# main_8.net
KiCad netlist of a schematic drawn in Altium Designer
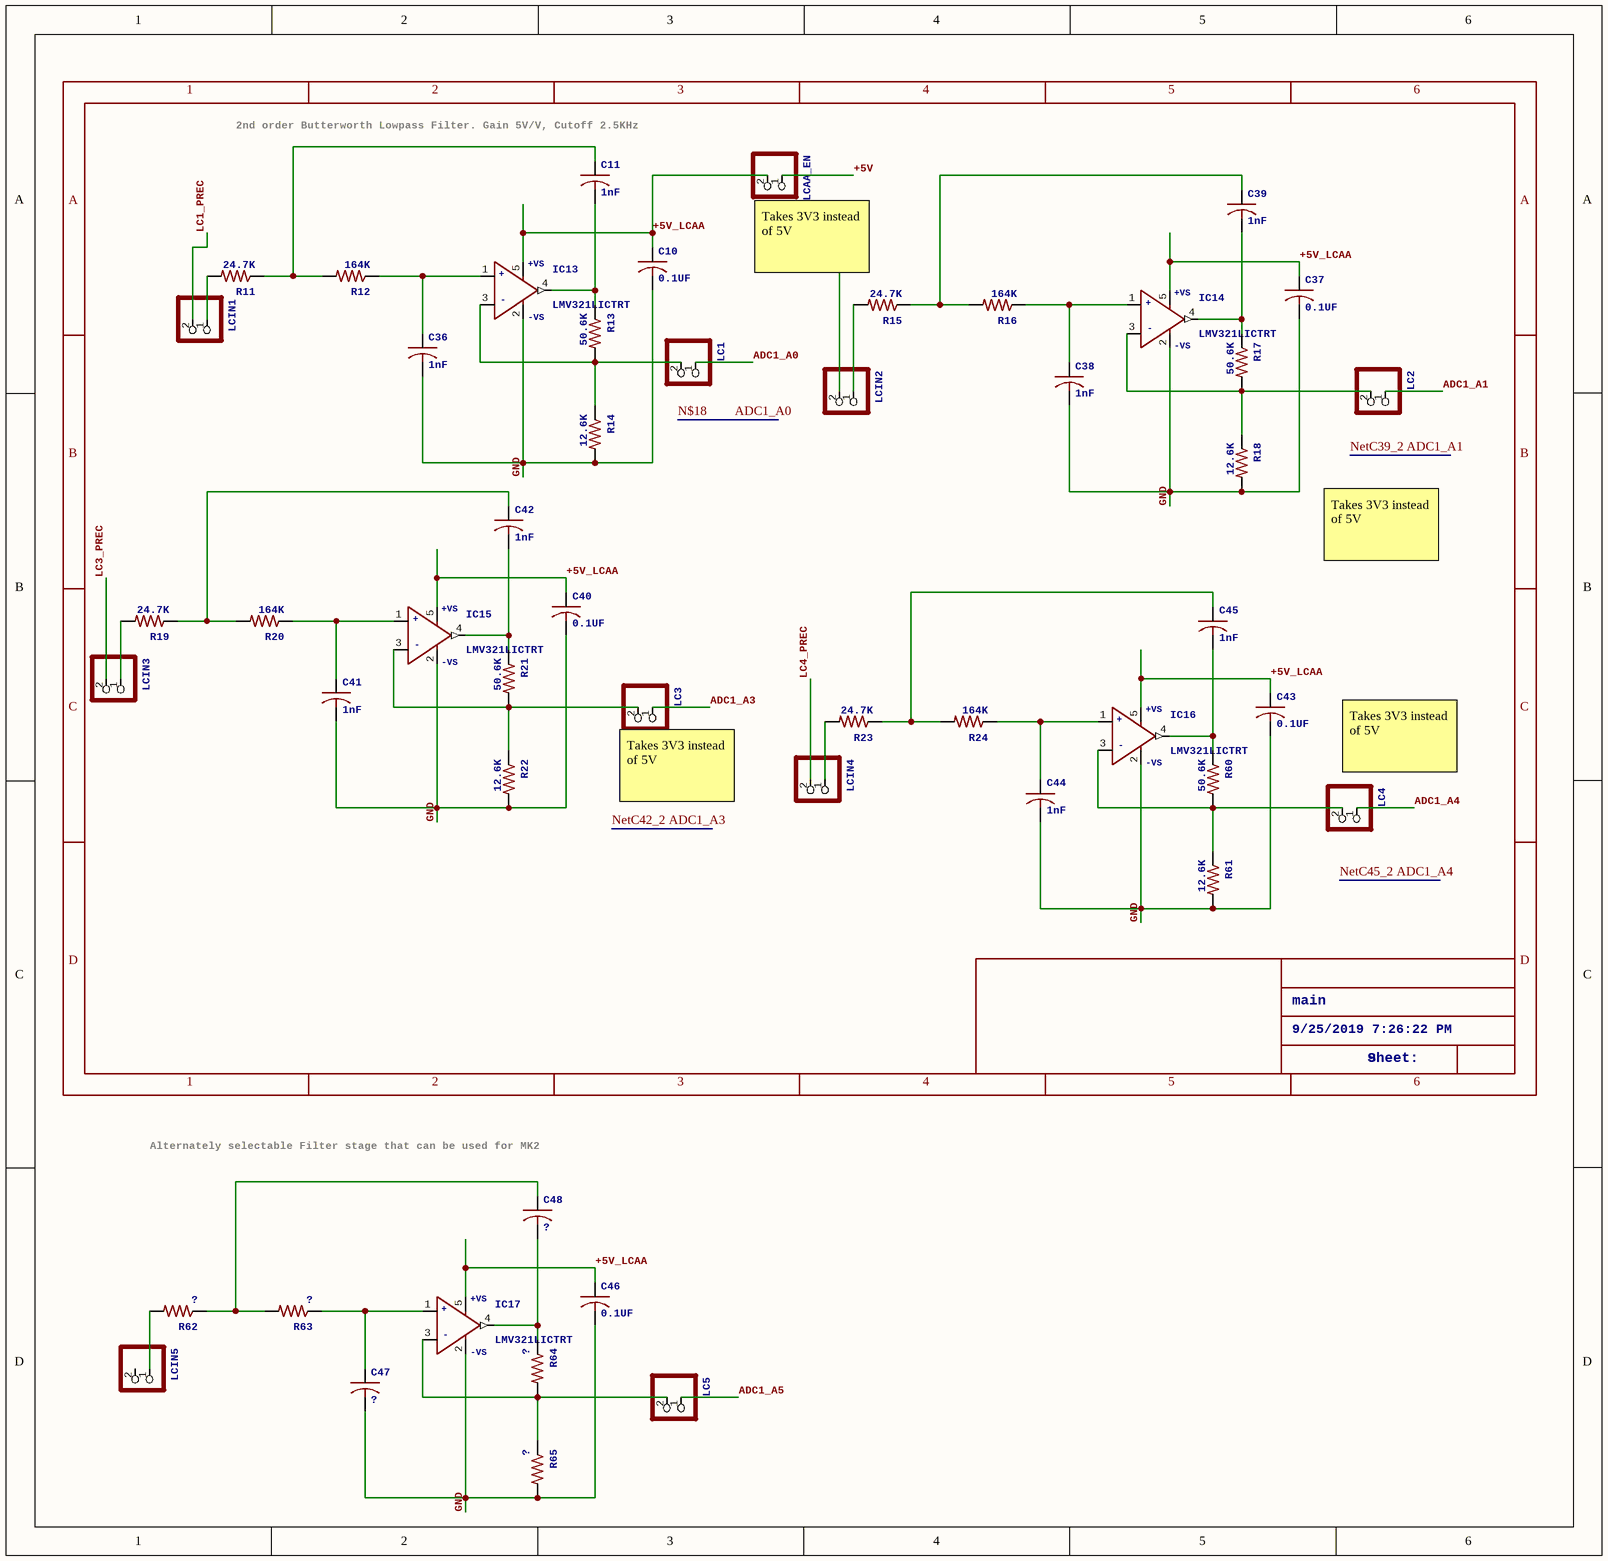
[diagram p0: main_8.SchDoc]

(export (version "E")
  (design (tool "Eeschema 10.0.6"))
  (components
    (comp (ref "C10")
      (value "0.1UF")
      (footprint "C0805")
      (description "CAPACITOR, American symbol")
      (libsource (lib "rcl") (part "C-USC0805"))
    )
    (comp (ref "C11")
      (value "1nF")
      (footprint "C0805")
      (description "CAPACITOR, American symbol")
      (libsource (lib "rcl") (part "C-USC0805"))
    )
    (comp (ref "C36")
      (value "1nF")
      (footprint "C0805")
      (description "CAPACITOR, American symbol")
      (libsource (lib "rcl") (part "C-USC0805"))
    )
    (comp (ref "C37")
      (value "0.1UF")
      (footprint "C0805")
      (description "CAPACITOR, American symbol")
      (libsource (lib "rcl") (part "C-USC0805"))
    )
    (comp (ref "C38")
      (value "1nF")
      (footprint "C0805")
      (description "CAPACITOR, American symbol")
      (libsource (lib "rcl") (part "C-USC0805"))
    )
    (comp (ref "C39")
      (value "1nF")
      (footprint "C0805")
      (description "CAPACITOR, American symbol")
      (libsource (lib "rcl") (part "C-USC0805"))
    )
    (comp (ref "C40")
      (value "0.1UF")
      (footprint "C0805")
      (description "CAPACITOR, American symbol")
      (libsource (lib "rcl") (part "C-USC0805"))
    )
    (comp (ref "C41")
      (value "1nF")
      (footprint "C0805")
      (description "CAPACITOR, American symbol")
      (libsource (lib "rcl") (part "C-USC0805"))
    )
    (comp (ref "C42")
      (value "1nF")
      (footprint "C0805")
      (description "CAPACITOR, American symbol")
      (libsource (lib "rcl") (part "C-USC0805"))
    )
    (comp (ref "C43")
      (value "0.1UF")
      (footprint "C0805")
      (description "CAPACITOR, American symbol")
      (libsource (lib "rcl") (part "C-USC0805"))
    )
    (comp (ref "C44")
      (value "1nF")
      (footprint "C0805")
      (description "CAPACITOR, American symbol")
      (libsource (lib "rcl") (part "C-USC0805"))
    )
    (comp (ref "C45")
      (value "1nF")
      (footprint "C0805")
      (description "CAPACITOR, American symbol")
      (libsource (lib "rcl") (part "C-USC0805"))
    )
    (comp (ref "C46")
      (value "0.1UF")
      (footprint "C0805")
      (description "CAPACITOR, American symbol")
      (libsource (lib "rcl") (part "C-USC0805"))
    )
    (comp (ref "C47")
      (value "?")
      (footprint "C0805")
      (description "CAPACITOR, American symbol")
      (libsource (lib "rcl") (part "C-USC0805"))
    )
    (comp (ref "C48")
      (value "?")
      (footprint "C0805")
      (description "CAPACITOR, American symbol")
      (libsource (lib "rcl") (part "C-USC0805"))
    )
    (comp (ref "IC13")
      (value "LMV321LICTRT")
      (footprint "SOT23-5")
      (fields
        (field (name "MF") "ALTERA CORPORATION")
        (field (name "MPN") "AD8065ARTZ-REEL7")
        (field (name "+") "+")
        (field (name "-") "-")
        (field (name "+VS") "+VS")
        (field (name "-VS") "-VS")
        (field (name "LIBRARYNAME") "st-microelectronics-extra")
      )
      (libsource (lib "st-microelectronics-extra") (part "LMV321LICTRT"))
    )
    (comp (ref "IC14")
      (value "LMV321LICTRT")
      (footprint "SOT23-5")
      (fields
        (field (name "MF") "ALTERA CORPORATION")
        (field (name "MPN") "AD8065ARTZ-REEL7")
        (field (name "+") "+")
        (field (name "-") "-")
        (field (name "+VS") "+VS")
        (field (name "-VS") "-VS")
        (field (name "LIBRARYNAME") "st-microelectronics-extra")
      )
      (libsource (lib "st-microelectronics-extra") (part "LMV321LICTRT"))
    )
    (comp (ref "IC15")
      (value "LMV321LICTRT")
      (footprint "SOT23-5")
      (fields
        (field (name "MF") "ALTERA CORPORATION")
        (field (name "MPN") "AD8065ARTZ-REEL7")
        (field (name "+") "+")
        (field (name "-") "-")
        (field (name "+VS") "+VS")
        (field (name "-VS") "-VS")
        (field (name "LIBRARYNAME") "st-microelectronics-extra")
      )
      (libsource (lib "st-microelectronics-extra") (part "LMV321LICTRT"))
    )
    (comp (ref "IC16")
      (value "LMV321LICTRT")
      (footprint "SOT23-5")
      (fields
        (field (name "MF") "ALTERA CORPORATION")
        (field (name "MPN") "AD8065ARTZ-REEL7")
        (field (name "+") "+")
        (field (name "-") "-")
        (field (name "+VS") "+VS")
        (field (name "-VS") "-VS")
        (field (name "LIBRARYNAME") "st-microelectronics-extra")
      )
      (libsource (lib "st-microelectronics-extra") (part "LMV321LICTRT"))
    )
    (comp (ref "IC17")
      (value "LMV321LICTRT")
      (footprint "SOT23-5")
      (fields
        (field (name "MF") "ALTERA CORPORATION")
        (field (name "MPN") "AD8065ARTZ-REEL7")
        (field (name "+") "+")
        (field (name "-") "-")
        (field (name "+VS") "+VS")
        (field (name "-VS") "-VS")
        (field (name "LIBRARYNAME") "st-microelectronics-extra")
      )
      (libsource (lib "st-microelectronics-extra") (part "LMV321LICTRT"))
    )
    (comp (ref "LC1")
      (value "PINHD-1X2")
      (footprint "1X02")
      (description "PIN HEADER")
      (fields (field (name "LIBRARYNAME") "pinhead"))
      (libsource (lib "pinhead") (part "PINHD-1X2"))
    )
    (comp (ref "LC2")
      (value "PINHD-1X2")
      (footprint "1X02")
      (description "PIN HEADER")
      (fields (field (name "LIBRARYNAME") "pinhead"))
      (libsource (lib "pinhead") (part "PINHD-1X2"))
    )
    (comp (ref "LC3")
      (value "PINHD-1X2")
      (footprint "1X02")
      (description "PIN HEADER")
      (fields (field (name "LIBRARYNAME") "pinhead"))
      (libsource (lib "pinhead") (part "PINHD-1X2"))
    )
    (comp (ref "LC4")
      (value "PINHD-1X2")
      (footprint "1X02")
      (description "PIN HEADER")
      (fields (field (name "LIBRARYNAME") "pinhead"))
      (libsource (lib "pinhead") (part "PINHD-1X2"))
    )
    (comp (ref "LC5")
      (value "PINHD-1X2")
      (footprint "1X02")
      (description "PIN HEADER")
      (fields (field (name "LIBRARYNAME") "pinhead"))
      (libsource (lib "pinhead") (part "PINHD-1X2"))
    )
    (comp (ref "LCAA_EN")
      (value "PINHD-1X2")
      (footprint "1X02")
      (description "PIN HEADER")
      (fields (field (name "LIBRARYNAME") "pinhead"))
      (libsource (lib "pinhead") (part "PINHD-1X2"))
    )
    (comp (ref "LCIN1")
      (value "PINHD-1X2")
      (footprint "1X02")
      (description "PIN HEADER")
      (fields (field (name "LIBRARYNAME") "pinhead"))
      (libsource (lib "pinhead") (part "PINHD-1X2"))
    )
    (comp (ref "LCIN2")
      (value "PINHD-1X2")
      (footprint "1X02")
      (description "PIN HEADER")
      (fields (field (name "LIBRARYNAME") "pinhead"))
      (libsource (lib "pinhead") (part "PINHD-1X2"))
    )
    (comp (ref "LCIN3")
      (value "PINHD-1X2")
      (footprint "1X02")
      (description "PIN HEADER")
      (fields (field (name "LIBRARYNAME") "pinhead"))
      (libsource (lib "pinhead") (part "PINHD-1X2"))
    )
    (comp (ref "LCIN4")
      (value "PINHD-1X2")
      (footprint "1X02")
      (description "PIN HEADER")
      (fields (field (name "LIBRARYNAME") "pinhead"))
      (libsource (lib "pinhead") (part "PINHD-1X2"))
    )
    (comp (ref "LCIN5")
      (value "PINHD-1X2")
      (footprint "1X02")
      (description "PIN HEADER")
      (fields (field (name "LIBRARYNAME") "pinhead"))
      (libsource (lib "pinhead") (part "PINHD-1X2"))
    )
    (comp (ref "R11")
      (value "24.7K")
      (footprint "R0805")
      (description "RESISTOR, American symbol")
      (libsource (lib "rcl") (part "R-US_R0805"))
    )
    (comp (ref "R12")
      (value "164K")
      (footprint "R0805")
      (description "RESISTOR, American symbol")
      (libsource (lib "rcl") (part "R-US_R0805"))
    )
    (comp (ref "R13")
      (value "50.6K")
      (footprint "R0805")
      (description "RESISTOR, American symbol")
      (libsource (lib "rcl") (part "R-US_R0805"))
    )
    (comp (ref "R14")
      (value "12.6K")
      (footprint "R0805")
      (description "RESISTOR, American symbol")
      (libsource (lib "rcl") (part "R-US_R0805"))
    )
    (comp (ref "R15")
      (value "24.7K")
      (footprint "R0805")
      (description "RESISTOR, American symbol")
      (libsource (lib "rcl") (part "R-US_R0805"))
    )
    (comp (ref "R16")
      (value "164K")
      (footprint "R0805")
      (description "RESISTOR, American symbol")
      (libsource (lib "rcl") (part "R-US_R0805"))
    )
    (comp (ref "R17")
      (value "50.6K")
      (footprint "R0805")
      (description "RESISTOR, American symbol")
      (libsource (lib "rcl") (part "R-US_R0805"))
    )
    (comp (ref "R18")
      (value "12.6K")
      (footprint "R0805")
      (description "RESISTOR, American symbol")
      (libsource (lib "rcl") (part "R-US_R0805"))
    )
    (comp (ref "R19")
      (value "24.7K")
      (footprint "R0805")
      (description "RESISTOR, American symbol")
      (libsource (lib "rcl") (part "R-US_R0805"))
    )
    (comp (ref "R20")
      (value "164K")
      (footprint "R0805")
      (description "RESISTOR, American symbol")
      (libsource (lib "rcl") (part "R-US_R0805"))
    )
    (comp (ref "R21")
      (value "50.6K")
      (footprint "R0805")
      (description "RESISTOR, American symbol")
      (libsource (lib "rcl") (part "R-US_R0805"))
    )
    (comp (ref "R22")
      (value "12.6K")
      (footprint "R0805")
      (description "RESISTOR, American symbol")
      (libsource (lib "rcl") (part "R-US_R0805"))
    )
    (comp (ref "R23")
      (value "24.7K")
      (footprint "R0805")
      (description "RESISTOR, American symbol")
      (libsource (lib "rcl") (part "R-US_R0805"))
    )
    (comp (ref "R24")
      (value "164K")
      (footprint "R0805")
      (description "RESISTOR, American symbol")
      (libsource (lib "rcl") (part "R-US_R0805"))
    )
    (comp (ref "R60")
      (value "50.6K")
      (footprint "R0805")
      (description "RESISTOR, American symbol")
      (libsource (lib "rcl") (part "R-US_R0805"))
    )
    (comp (ref "R61")
      (value "12.6K")
      (footprint "R0805")
      (description "RESISTOR, American symbol")
      (libsource (lib "rcl") (part "R-US_R0805"))
    )
    (comp (ref "R62")
      (value "?")
      (footprint "R0805")
      (description "RESISTOR, American symbol")
      (libsource (lib "rcl") (part "R-US_R0805"))
    )
    (comp (ref "R63")
      (value "?")
      (footprint "R0805")
      (description "RESISTOR, American symbol")
      (libsource (lib "rcl") (part "R-US_R0805"))
    )
    (comp (ref "R64")
      (value "?")
      (footprint "R0805")
      (description "RESISTOR, American symbol")
      (libsource (lib "rcl") (part "R-US_R0805"))
    )
    (comp (ref "R65")
      (value "?")
      (footprint "R0805")
      (description "RESISTOR, American symbol")
      (libsource (lib "rcl") (part "R-US_R0805"))
    )
  )
  (nets
    (net (code "1") (name "/+5V") (class "Default")
      (node (ref "LCAA_EN") (pin "1") (pinfunction "1_1") (pintype "passive"))
    )
    (net (code "2") (name "/+5V_LCAA") (class "Default")
      (node (ref "C10") (pin "1") (pinfunction "1_1") (pintype "passive"))
      (node (ref "C37") (pin "1") (pinfunction "1_1") (pintype "passive"))
      (node (ref "C40") (pin "1") (pinfunction "1_1") (pintype "passive"))
      (node (ref "C43") (pin "1") (pinfunction "1_1") (pintype "passive"))
      (node (ref "C46") (pin "1") (pinfunction "1_1") (pintype "passive"))
      (node (ref "IC13") (pin "5") (pinfunction "+VS_5") (pintype "passive"))
      (node (ref "IC14") (pin "5") (pinfunction "+VS_5") (pintype "passive"))
      (node (ref "IC15") (pin "5") (pinfunction "+VS_5") (pintype "passive"))
      (node (ref "IC16") (pin "5") (pinfunction "+VS_5") (pintype "passive"))
      (node (ref "IC17") (pin "5") (pinfunction "+VS_5") (pintype "passive"))
      (node (ref "LCAA_EN") (pin "2") (pinfunction "2_2") (pintype "passive"))
    )
    (net (code "3") (name "/ADC1_A0") (class "Default")
      (node (ref "LC1") (pin "1") (pinfunction "1_1") (pintype "passive"))
    )
    (net (code "4") (name "/ADC1_A1") (class "Default")
      (node (ref "LC2") (pin "1") (pinfunction "1_1") (pintype "passive"))
    )
    (net (code "5") (name "/ADC1_A3") (class "Default")
      (node (ref "LC3") (pin "1") (pinfunction "1_1") (pintype "passive"))
    )
    (net (code "6") (name "/ADC1_A4") (class "Default")
      (node (ref "LC4") (pin "1") (pinfunction "1_1") (pintype "passive"))
    )
    (net (code "7") (name "/ADC1_A5") (class "Default")
      (node (ref "LC5") (pin "1") (pinfunction "1_1") (pintype "passive"))
    )
    (net (code "8") (name "/GND") (class "Default")
      (node (ref "C10") (pin "2") (pinfunction "2_2") (pintype "passive"))
      (node (ref "C36") (pin "2") (pinfunction "2_2") (pintype "passive"))
      (node (ref "C37") (pin "2") (pinfunction "2_2") (pintype "passive"))
      (node (ref "C38") (pin "2") (pinfunction "2_2") (pintype "passive"))
      (node (ref "C40") (pin "2") (pinfunction "2_2") (pintype "passive"))
      (node (ref "C41") (pin "2") (pinfunction "2_2") (pintype "passive"))
      (node (ref "C43") (pin "2") (pinfunction "2_2") (pintype "passive"))
      (node (ref "C44") (pin "2") (pinfunction "2_2") (pintype "passive"))
      (node (ref "C46") (pin "2") (pinfunction "2_2") (pintype "passive"))
      (node (ref "C47") (pin "2") (pinfunction "2_2") (pintype "passive"))
      (node (ref "IC13") (pin "2") (pinfunction "-VS_2") (pintype "passive"))
      (node (ref "IC14") (pin "2") (pinfunction "-VS_2") (pintype "passive"))
      (node (ref "IC15") (pin "2") (pinfunction "-VS_2") (pintype "passive"))
      (node (ref "IC16") (pin "2") (pinfunction "-VS_2") (pintype "passive"))
      (node (ref "IC17") (pin "2") (pinfunction "-VS_2") (pintype "passive"))
      (node (ref "R14") (pin "2") (pinfunction "2_2") (pintype "passive"))
      (node (ref "R18") (pin "2") (pinfunction "2_2") (pintype "passive"))
      (node (ref "R22") (pin "2") (pinfunction "2_2") (pintype "passive"))
      (node (ref "R61") (pin "2") (pinfunction "2_2") (pintype "passive"))
      (node (ref "R65") (pin "2") (pinfunction "2_2") (pintype "passive"))
    )
    (net (code "9") (name "/LC1_PREC") (class "Default")
      (node (ref "LCIN1") (pin "2") (pinfunction "2_2") (pintype "passive"))
    )
    (net (code "10") (name "/LC2_PREC") (class "Default")
      (node (ref "LCIN2") (pin "2") (pinfunction "2_2") (pintype "passive"))
    )
    (net (code "11") (name "/LC3_PREC") (class "Default")
      (node (ref "LCIN3") (pin "2") (pinfunction "2_2") (pintype "passive"))
    )
    (net (code "12") (name "/LC4_PREC") (class "Default")
      (node (ref "LCIN4") (pin "2") (pinfunction "2_2") (pintype "passive"))
    )
    (net (code "13") (name "Net-(C11-Pad1)") (class "Default")
      (node (ref "C11") (pin "1") (pinfunction "1_1") (pintype "passive"))
      (node (ref "R11") (pin "1") (pinfunction "1_1") (pintype "passive"))
      (node (ref "R12") (pin "2") (pinfunction "2_2") (pintype "passive"))
    )
    (net (code "14") (name "Net-(C39-Pad1)") (class "Default")
      (node (ref "C39") (pin "1") (pinfunction "1_1") (pintype "passive"))
      (node (ref "R15") (pin "1") (pinfunction "1_1") (pintype "passive"))
      (node (ref "R16") (pin "2") (pinfunction "2_2") (pintype "passive"))
    )
    (net (code "15") (name "Net-(C42-Pad1)") (class "Default")
      (node (ref "C42") (pin "1") (pinfunction "1_1") (pintype "passive"))
      (node (ref "R19") (pin "1") (pinfunction "1_1") (pintype "passive"))
      (node (ref "R20") (pin "2") (pinfunction "2_2") (pintype "passive"))
    )
    (net (code "16") (name "Net-(C45-Pad1)") (class "Default")
      (node (ref "C45") (pin "1") (pinfunction "1_1") (pintype "passive"))
      (node (ref "R23") (pin "1") (pinfunction "1_1") (pintype "passive"))
      (node (ref "R24") (pin "2") (pinfunction "2_2") (pintype "passive"))
    )
    (net (code "17") (name "Net-(C48-Pad1)") (class "Default")
      (node (ref "C48") (pin "1") (pinfunction "1_1") (pintype "passive"))
      (node (ref "R62") (pin "1") (pinfunction "1_1") (pintype "passive"))
      (node (ref "R63") (pin "2") (pinfunction "2_2") (pintype "passive"))
    )
    (net (code "18") (name "Net-(IC13-IN+)") (class "Default")
      (node (ref "C36") (pin "1") (pinfunction "1_1") (pintype "passive"))
      (node (ref "IC13") (pin "1") (pinfunction "IN+_1") (pintype "passive"))
      (node (ref "R12") (pin "1") (pinfunction "1_1") (pintype "passive"))
    )
    (net (code "19") (name "Net-(IC13-IN-)") (class "Default")
      (node (ref "IC13") (pin "3") (pinfunction "IN-_3") (pintype "passive"))
      (node (ref "LC1") (pin "2") (pinfunction "2_2") (pintype "passive"))
      (node (ref "R13") (pin "2") (pinfunction "2_2") (pintype "passive"))
      (node (ref "R14") (pin "1") (pinfunction "1_1") (pintype "passive"))
    )
    (net (code "20") (name "Net-(IC13-OUT)") (class "Default")
      (node (ref "C11") (pin "2") (pinfunction "2_2") (pintype "passive"))
      (node (ref "IC13") (pin "4") (pinfunction "OUT_4") (pintype "output"))
      (node (ref "R13") (pin "1") (pinfunction "1_1") (pintype "passive"))
    )
    (net (code "21") (name "Net-(IC14-IN+)") (class "Default")
      (node (ref "C38") (pin "1") (pinfunction "1_1") (pintype "passive"))
      (node (ref "IC14") (pin "1") (pinfunction "IN+_1") (pintype "passive"))
      (node (ref "R16") (pin "1") (pinfunction "1_1") (pintype "passive"))
    )
    (net (code "22") (name "Net-(IC14-IN-)") (class "Default")
      (node (ref "IC14") (pin "3") (pinfunction "IN-_3") (pintype "passive"))
      (node (ref "LC2") (pin "2") (pinfunction "2_2") (pintype "passive"))
      (node (ref "R17") (pin "2") (pinfunction "2_2") (pintype "passive"))
      (node (ref "R18") (pin "1") (pinfunction "1_1") (pintype "passive"))
    )
    (net (code "23") (name "Net-(IC14-OUT)") (class "Default")
      (node (ref "C39") (pin "2") (pinfunction "2_2") (pintype "passive"))
      (node (ref "IC14") (pin "4") (pinfunction "OUT_4") (pintype "output"))
      (node (ref "R17") (pin "1") (pinfunction "1_1") (pintype "passive"))
    )
    (net (code "24") (name "Net-(IC15-IN+)") (class "Default")
      (node (ref "C41") (pin "1") (pinfunction "1_1") (pintype "passive"))
      (node (ref "IC15") (pin "1") (pinfunction "IN+_1") (pintype "passive"))
      (node (ref "R20") (pin "1") (pinfunction "1_1") (pintype "passive"))
    )
    (net (code "25") (name "Net-(IC15-IN-)") (class "Default")
      (node (ref "IC15") (pin "3") (pinfunction "IN-_3") (pintype "passive"))
      (node (ref "LC3") (pin "2") (pinfunction "2_2") (pintype "passive"))
      (node (ref "R21") (pin "2") (pinfunction "2_2") (pintype "passive"))
      (node (ref "R22") (pin "1") (pinfunction "1_1") (pintype "passive"))
    )
    (net (code "26") (name "Net-(IC15-OUT)") (class "Default")
      (node (ref "C42") (pin "2") (pinfunction "2_2") (pintype "passive"))
      (node (ref "IC15") (pin "4") (pinfunction "OUT_4") (pintype "output"))
      (node (ref "R21") (pin "1") (pinfunction "1_1") (pintype "passive"))
    )
    (net (code "27") (name "Net-(IC16-IN+)") (class "Default")
      (node (ref "C44") (pin "1") (pinfunction "1_1") (pintype "passive"))
      (node (ref "IC16") (pin "1") (pinfunction "IN+_1") (pintype "passive"))
      (node (ref "R24") (pin "1") (pinfunction "1_1") (pintype "passive"))
    )
    (net (code "28") (name "Net-(IC16-IN-)") (class "Default")
      (node (ref "IC16") (pin "3") (pinfunction "IN-_3") (pintype "passive"))
      (node (ref "LC4") (pin "2") (pinfunction "2_2") (pintype "passive"))
      (node (ref "R60") (pin "2") (pinfunction "2_2") (pintype "passive"))
      (node (ref "R61") (pin "1") (pinfunction "1_1") (pintype "passive"))
    )
    (net (code "29") (name "Net-(IC16-OUT)") (class "Default")
      (node (ref "C45") (pin "2") (pinfunction "2_2") (pintype "passive"))
      (node (ref "IC16") (pin "4") (pinfunction "OUT_4") (pintype "output"))
      (node (ref "R60") (pin "1") (pinfunction "1_1") (pintype "passive"))
    )
    (net (code "30") (name "Net-(IC17-IN+)") (class "Default")
      (node (ref "C47") (pin "1") (pinfunction "1_1") (pintype "passive"))
      (node (ref "IC17") (pin "1") (pinfunction "IN+_1") (pintype "passive"))
      (node (ref "R63") (pin "1") (pinfunction "1_1") (pintype "passive"))
    )
    (net (code "31") (name "Net-(IC17-IN-)") (class "Default")
      (node (ref "IC17") (pin "3") (pinfunction "IN-_3") (pintype "passive"))
      (node (ref "LC5") (pin "2") (pinfunction "2_2") (pintype "passive"))
      (node (ref "R64") (pin "2") (pinfunction "2_2") (pintype "passive"))
      (node (ref "R65") (pin "1") (pinfunction "1_1") (pintype "passive"))
    )
    (net (code "32") (name "Net-(IC17-OUT)") (class "Default")
      (node (ref "C48") (pin "2") (pinfunction "2_2") (pintype "passive"))
      (node (ref "IC17") (pin "4") (pinfunction "OUT_4") (pintype "output"))
      (node (ref "R64") (pin "1") (pinfunction "1_1") (pintype "passive"))
    )
    (net (code "33") (name "Net-(LCIN1-Pad1)") (class "Default")
      (node (ref "LCIN1") (pin "1") (pinfunction "1_1") (pintype "passive"))
      (node (ref "R11") (pin "2") (pinfunction "2_2") (pintype "passive"))
    )
    (net (code "34") (name "Net-(LCIN2-Pad1)") (class "Default")
      (node (ref "LCIN2") (pin "1") (pinfunction "1_1") (pintype "passive"))
      (node (ref "R15") (pin "2") (pinfunction "2_2") (pintype "passive"))
    )
    (net (code "35") (name "Net-(LCIN3-Pad1)") (class "Default")
      (node (ref "LCIN3") (pin "1") (pinfunction "1_1") (pintype "passive"))
      (node (ref "R19") (pin "2") (pinfunction "2_2") (pintype "passive"))
    )
    (net (code "36") (name "Net-(LCIN4-Pad1)") (class "Default")
      (node (ref "LCIN4") (pin "1") (pinfunction "1_1") (pintype "passive"))
      (node (ref "R23") (pin "2") (pinfunction "2_2") (pintype "passive"))
    )
    (net (code "37") (name "Net-(LCIN5-Pad1)") (class "Default")
      (node (ref "LCIN5") (pin "1") (pinfunction "1_1") (pintype "passive"))
      (node (ref "R62") (pin "2") (pinfunction "2_2") (pintype "passive"))
    )
    (net (code "38") (name "unconnected-(LCIN5-Pad2)") (class "Default")
      (node (ref "LCIN5") (pin "2") (pinfunction "2_2") (pintype "passive"))
    )
  )
)
